# Moteino_Trail_Counter.net
KiCad netlist of a schematic drawn in EAGLE
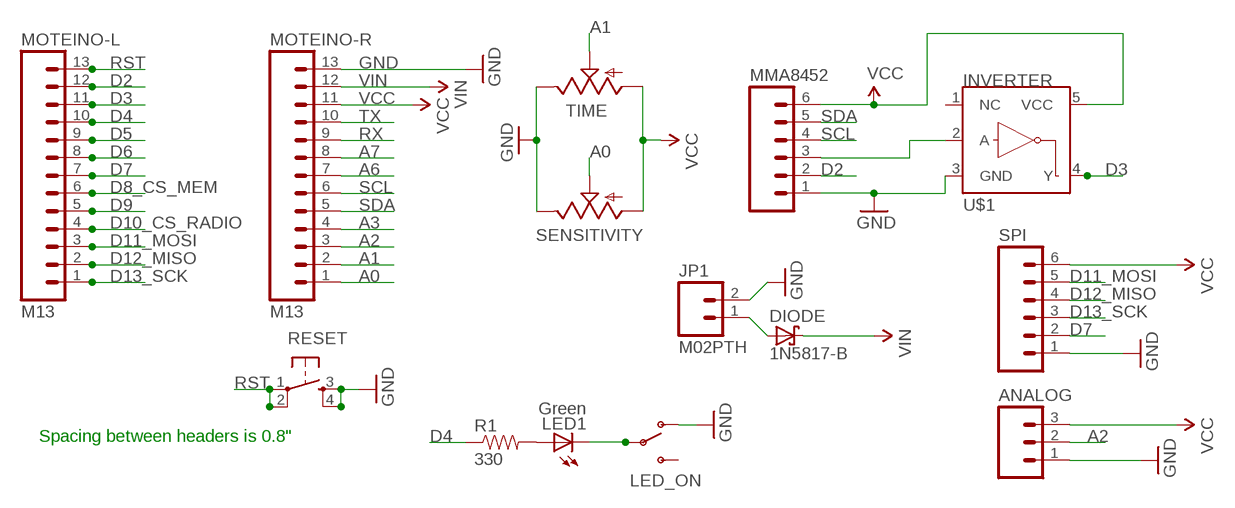
[diagram p0: schematic, sheet 1]

(export (version "E")
  (design (tool "Eeschema 10.0.6"))
  (components
    (comp (ref "ANALOG")
      (value "M03LOCK")
      (footprint "eagle-import:1X03_LOCK")
      (libsource (lib "eagle-import") (part "M03LOCK"))
    )
    (comp (ref "DIODE")
      (value "1N5817-B")
      (footprint "eagle-import:DO41-7.6")
      (libsource (lib "eagle-import") (part "1N5817-B"))
    )
    (comp (ref "JP1")
      (value "M02PTH")
      (footprint "eagle-import:1X02")
      (libsource (lib "eagle-import") (part "M02PTH"))
    )
    (comp (ref "LED1")
      (value "Green")
      (footprint "eagle-import:LED3MM")
      (libsource (lib "eagle-import") (part "LED3MM"))
    )
    (comp (ref "LED_ON")
      (value "SWITCH-SPDTPTH")
      (footprint "eagle-import:SWITCH-SPDT")
      (libsource (lib "eagle-import") (part "SWITCH-SPDTPTH"))
    )
    (comp (ref "MMA8452")
      (value "M06LOCK")
      (footprint "eagle-import:1X06_LOCK")
      (libsource (lib "eagle-import") (part "M06LOCK"))
    )
    (comp (ref "MOTEINO-L")
      (value "M13")
      (footprint "eagle-import:1X13")
      (libsource (lib "eagle-import") (part "M13"))
    )
    (comp (ref "MOTEINO-R")
      (value "M13")
      (footprint "eagle-import:1X13")
      (libsource (lib "eagle-import") (part "M13"))
    )
    (comp (ref "R1")
      (value "330")
      (footprint "eagle-import:AXIAL-0.3")
      (libsource (lib "eagle-import") (part "RESISTORAXIAL-0.3"))
    )
    (comp (ref "RESET")
      (value "TAC_SWITCHPTH")
      (footprint "eagle-import:TACTILE-PTH")
      (libsource (lib "eagle-import") (part "TAC_SWITCHPTH"))
    )
    (comp (ref "SENSITIVITY")
      (value "TRIM_US-B25U")
      (footprint "eagle-import:B25U")
      (libsource (lib "eagle-import") (part "TRIM_US-B25U"))
    )
    (comp (ref "SPI")
      (value "M06LOCK")
      (footprint "eagle-import:1X06_LOCK")
      (libsource (lib "eagle-import") (part "M06LOCK"))
    )
    (comp (ref "TIME")
      (value "TRIM_US-B25U")
      (footprint "eagle-import:B25U")
      (libsource (lib "eagle-import") (part "TRIM_US-B25U"))
    )
    (comp (ref "U$1")
      (value "INVERTER")
      (footprint "eagle-import:SOT23-5")
      (libsource (lib "eagle-import") (part "INVERTER"))
    )
  )
  (nets
    (net (code "1") (name "/A0") (class "Default")
      (node (ref "MOTEINO-R") (pin "1") (pinfunction "1_1") (pintype "passive"))
      (node (ref "SENSITIVITY") (pin "S") (pinfunction "S_S") (pintype "passive"))
    )
    (net (code "2") (name "/A1") (class "Default")
      (node (ref "MOTEINO-R") (pin "2") (pinfunction "2_2") (pintype "passive"))
      (node (ref "TIME") (pin "S") (pinfunction "S_S") (pintype "passive"))
    )
    (net (code "3") (name "/A2") (class "Default")
      (node (ref "ANALOG") (pin "2") (pinfunction "2_2") (pintype "passive"))
      (node (ref "MOTEINO-R") (pin "3") (pinfunction "3_3") (pintype "passive"))
    )
    (net (code "4") (name "/A3") (class "Default")
      (node (ref "MOTEINO-R") (pin "4") (pinfunction "4_4") (pintype "passive"))
    )
    (net (code "5") (name "/A6") (class "Default")
      (node (ref "MOTEINO-R") (pin "7") (pinfunction "7_7") (pintype "passive"))
    )
    (net (code "6") (name "/A7") (class "Default")
      (node (ref "MOTEINO-R") (pin "8") (pinfunction "8_8") (pintype "passive"))
    )
    (net (code "7") (name "/D2") (class "Default")
      (node (ref "MMA8452") (pin "2") (pinfunction "2_2") (pintype "passive"))
      (node (ref "MOTEINO-L") (pin "12") (pinfunction "12_12") (pintype "passive"))
    )
    (net (code "8") (name "/D3") (class "Default")
      (node (ref "MOTEINO-L") (pin "11") (pinfunction "11_11") (pintype "passive"))
      (node (ref "U$1") (pin "4") (pinfunction "Y_4") (pintype "bidirectional"))
    )
    (net (code "9") (name "/D4") (class "Default")
      (node (ref "MOTEINO-L") (pin "10") (pinfunction "10_10") (pintype "passive"))
      (node (ref "R1") (pin "P$1") (pinfunction "1_P$1") (pintype "passive"))
    )
    (net (code "10") (name "/D5") (class "Default")
      (node (ref "MOTEINO-L") (pin "9") (pinfunction "9_9") (pintype "passive"))
    )
    (net (code "11") (name "/D6") (class "Default")
      (node (ref "MOTEINO-L") (pin "8") (pinfunction "8_8") (pintype "passive"))
    )
    (net (code "12") (name "/D7") (class "Default")
      (node (ref "MOTEINO-L") (pin "7") (pinfunction "7_7") (pintype "passive"))
      (node (ref "SPI") (pin "2") (pinfunction "2_2") (pintype "passive"))
    )
    (net (code "13") (name "/D8_CS_MEM") (class "Default")
      (node (ref "MOTEINO-L") (pin "6") (pinfunction "6_6") (pintype "passive"))
    )
    (net (code "14") (name "/D9") (class "Default")
      (node (ref "MOTEINO-L") (pin "5") (pinfunction "5_5") (pintype "passive"))
    )
    (net (code "15") (name "/D10_CS_RADIO") (class "Default")
      (node (ref "MOTEINO-L") (pin "4") (pinfunction "4_4") (pintype "passive"))
    )
    (net (code "16") (name "/D11_MOSI") (class "Default")
      (node (ref "MOTEINO-L") (pin "3") (pinfunction "3_3") (pintype "passive"))
      (node (ref "SPI") (pin "5") (pinfunction "5_5") (pintype "passive"))
    )
    (net (code "17") (name "/D12_MISO") (class "Default")
      (node (ref "MOTEINO-L") (pin "2") (pinfunction "2_2") (pintype "passive"))
      (node (ref "SPI") (pin "4") (pinfunction "4_4") (pintype "passive"))
    )
    (net (code "18") (name "/D13_SCK") (class "Default")
      (node (ref "MOTEINO-L") (pin "1") (pinfunction "1_1") (pintype "passive"))
      (node (ref "SPI") (pin "3") (pinfunction "3_3") (pintype "passive"))
    )
    (net (code "19") (name "/RST") (class "Default")
      (node (ref "MOTEINO-L") (pin "13") (pinfunction "13_13") (pintype "passive"))
      (node (ref "RESET") (pin "1") (pinfunction "1_1") (pintype "passive"))
      (node (ref "RESET") (pin "2") (pinfunction "2_2") (pintype "passive"))
    )
    (net (code "20") (name "/RX") (class "Default")
      (node (ref "MOTEINO-R") (pin "9") (pinfunction "9_9") (pintype "passive"))
    )
    (net (code "21") (name "/SCL") (class "Default")
      (node (ref "MMA8452") (pin "4") (pinfunction "4_4") (pintype "passive"))
      (node (ref "MOTEINO-R") (pin "6") (pinfunction "6_6") (pintype "passive"))
    )
    (net (code "22") (name "/SDA") (class "Default")
      (node (ref "MMA8452") (pin "5") (pinfunction "5_5") (pintype "passive"))
      (node (ref "MOTEINO-R") (pin "5") (pinfunction "5_5") (pintype "passive"))
    )
    (net (code "23") (name "/TX") (class "Default")
      (node (ref "MOTEINO-R") (pin "10") (pinfunction "10_10") (pintype "passive"))
    )
    (net (code "24") (name "GND") (class "Default")
      (node (ref "ANALOG") (pin "1") (pinfunction "1_1") (pintype "passive"))
      (node (ref "JP1") (pin "2") (pinfunction "2_2") (pintype "passive"))
      (node (ref "LED_ON") (pin "1") (pinfunction "O_1") (pintype "passive"))
      (node (ref "MMA8452") (pin "1") (pinfunction "1_1") (pintype "passive"))
      (node (ref "MOTEINO-R") (pin "13") (pinfunction "13_13") (pintype "passive"))
      (node (ref "RESET") (pin "3") (pinfunction "3_3") (pintype "passive"))
      (node (ref "RESET") (pin "4") (pinfunction "4_4") (pintype "passive"))
      (node (ref "SENSITIVITY") (pin "E") (pinfunction "E_E") (pintype "passive"))
      (node (ref "SPI") (pin "1") (pinfunction "1_1") (pintype "passive"))
      (node (ref "TIME") (pin "E") (pinfunction "E_E") (pintype "passive"))
      (node (ref "U$1") (pin "3") (pinfunction "GND_3") (pintype "bidirectional"))
    )
    (net (code "25") (name "Net-(DIODE-PadA)") (class "Default")
      (node (ref "DIODE") (pin "A") (pinfunction "A_A") (pintype "passive"))
      (node (ref "JP1") (pin "1") (pinfunction "1_1") (pintype "passive"))
    )
    (net (code "26") (name "Net-(LED1-C)") (class "Default")
      (node (ref "LED1") (pin "K") (pinfunction "C_K") (pintype "passive"))
      (node (ref "LED_ON") (pin "2") (pinfunction "P_2") (pintype "passive"))
    )
    (net (code "27") (name "Net-(R1-2)") (class "Default")
      (node (ref "LED1") (pin "A") (pinfunction "A_A") (pintype "passive"))
      (node (ref "R1") (pin "P$2") (pinfunction "2_P$2") (pintype "passive"))
    )
    (net (code "28") (name "Net-(U$1-A)") (class "Default")
      (node (ref "MMA8452") (pin "3") (pinfunction "3_3") (pintype "passive"))
      (node (ref "U$1") (pin "2") (pinfunction "A_2") (pintype "bidirectional"))
    )
    (net (code "29") (name "VCC") (class "Default")
      (node (ref "ANALOG") (pin "3") (pinfunction "3_3") (pintype "passive"))
      (node (ref "MMA8452") (pin "6") (pinfunction "6_6") (pintype "passive"))
      (node (ref "MOTEINO-R") (pin "11") (pinfunction "11_11") (pintype "passive"))
      (node (ref "SENSITIVITY") (pin "A") (pinfunction "A_A") (pintype "passive"))
      (node (ref "SPI") (pin "6") (pinfunction "6_6") (pintype "passive"))
      (node (ref "TIME") (pin "A") (pinfunction "A_A") (pintype "passive"))
      (node (ref "U$1") (pin "5") (pinfunction "VCC_5") (pintype "bidirectional"))
    )
    (net (code "30") (name "VIN") (class "Default")
      (node (ref "DIODE") (pin "C") (pinfunction "C_C") (pintype "passive"))
      (node (ref "MOTEINO-R") (pin "12") (pinfunction "12_12") (pintype "passive"))
    )
    (net (code "31") (name "unconnected-(LED_ON-S-Pad3)") (class "Default")
      (node (ref "LED_ON") (pin "3") (pinfunction "S_3") (pintype "passive"))
    )
    (net (code "32") (name "unconnected-(U$1-NC-Pad1)") (class "Default")
      (node (ref "U$1") (pin "1") (pinfunction "NC_1") (pintype "bidirectional"))
    )
  )
)
